# ControlPWMSin.net
KiCad netlist of a schematic drawn in Altium Designer
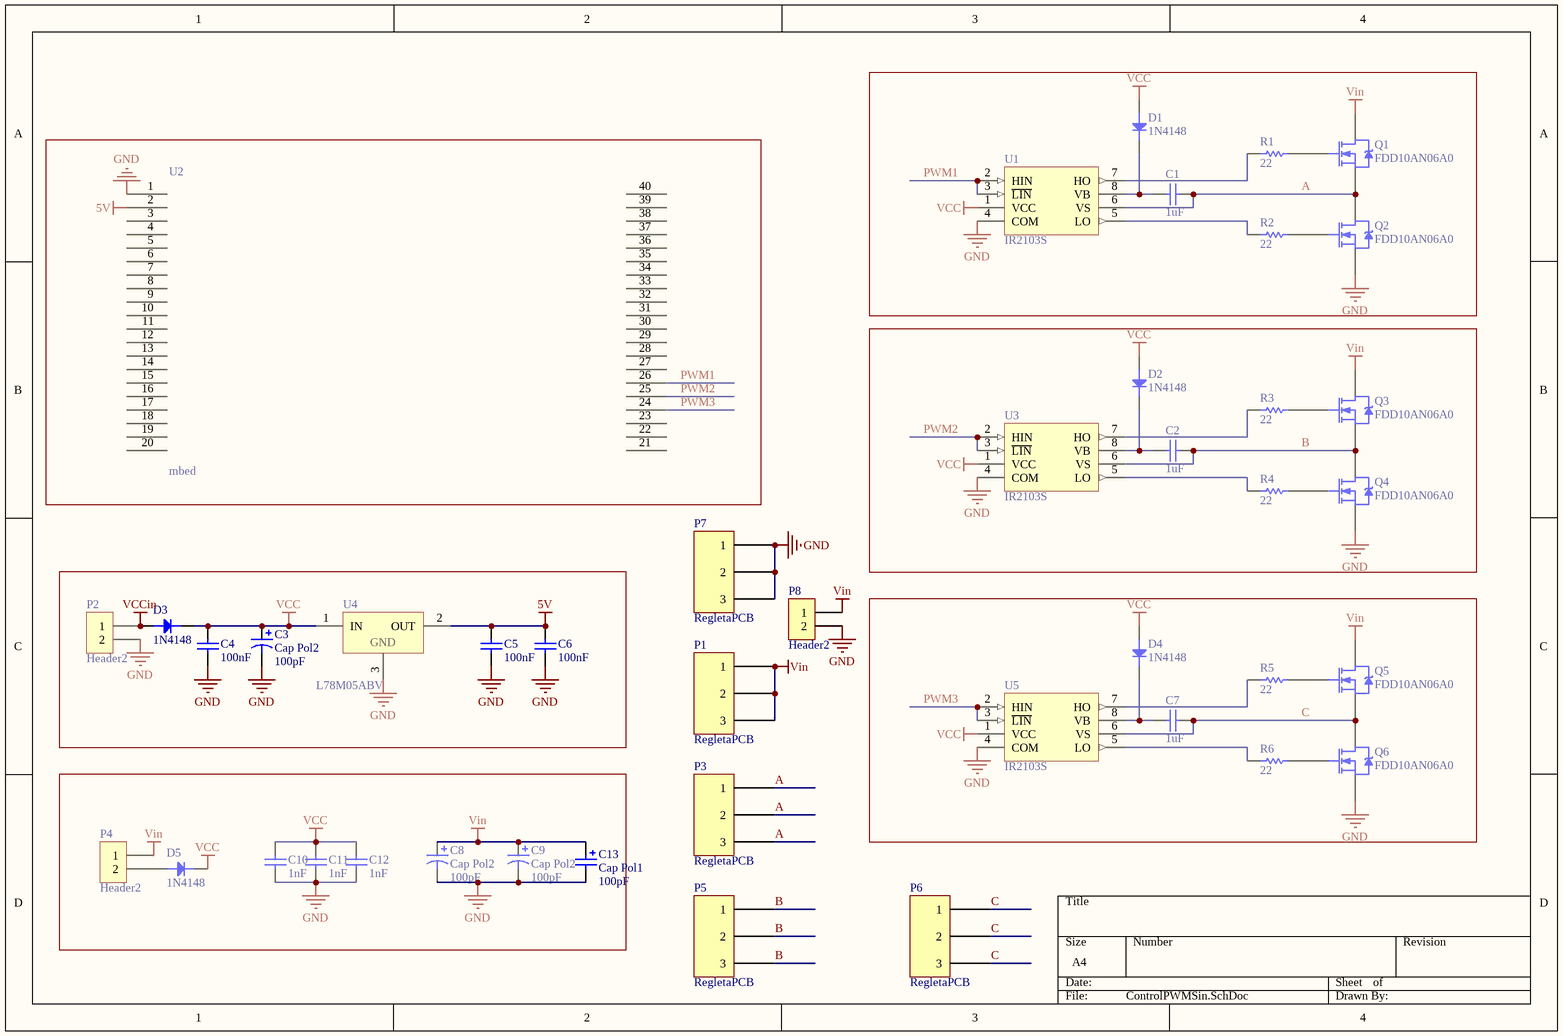
[diagram p0: ControlPWMSin.SchDoc]

(export (version "E")
  (design (tool "Eeschema 10.0.6"))
  (components
    (comp (ref "C1")
      (value "1uF")
      (footprint "0805_CAP")
      (fields (field (name "Comment") "Capacitor"))
      (libsource (lib "epf") (part "Cap"))
    )
    (comp (ref "C2")
      (value "1uF")
      (footprint "0805_CAP")
      (fields (field (name "Comment") "Capacitor"))
      (libsource (lib "epf") (part "Cap"))
    )
    (comp (ref "C3")
      (value "Cap Pol2")
      (footprint "TC7360-2924")
      (description "Polarized Capacitor (Axial)")
      (fields (field (name "ALTIUM_VALUE") "100pF") (field (name "PUBLISHER") "Altium Limited"))
      (libsource (lib "epf") (part "Cap Pol2"))
    )
    (comp (ref "C4")
      (value "100nF")
      (footprint "0805_CAP")
      (fields (field (name "Comment") "Capacitor"))
      (libsource (lib "epf") (part "Cap"))
    )
    (comp (ref "C5")
      (value "100nF")
      (footprint "0805_CAP")
      (fields (field (name "Comment") "Capacitor"))
      (libsource (lib "epf") (part "Cap"))
    )
    (comp (ref "C6")
      (value "100nF")
      (footprint "0805_CAP")
      (fields (field (name "Comment") "Capacitor"))
      (libsource (lib "epf") (part "Cap"))
    )
    (comp (ref "C7")
      (value "1uF")
      (footprint "0805_CAP")
      (fields (field (name "Comment") "Capacitor"))
      (libsource (lib "epf") (part "Cap"))
    )
    (comp (ref "C8")
      (value "Cap Pol2")
      (footprint "TC7360-2924")
      (description "Polarized Capacitor (Axial)")
      (fields (field (name "ALTIUM_VALUE") "100pF") (field (name "PUBLISHER") "Altium Limited"))
      (libsource (lib "epf") (part "Cap Pol2"))
    )
    (comp (ref "C9")
      (value "Cap Pol2")
      (footprint "TC7360-2924")
      (description "Polarized Capacitor (Axial)")
      (fields (field (name "ALTIUM_VALUE") "100pF") (field (name "PUBLISHER") "Altium Limited"))
      (libsource (lib "epf") (part "Cap Pol2"))
    )
    (comp (ref "C10")
      (value "1nF")
      (footprint "0805_CAP")
      (fields (field (name "Comment") "Capacitor"))
      (libsource (lib "epf") (part "Cap"))
    )
    (comp (ref "C11")
      (value "1nF")
      (footprint "0805_CAP")
      (fields (field (name "Comment") "Capacitor"))
      (libsource (lib "epf") (part "Cap"))
    )
    (comp (ref "C12")
      (value "1nF")
      (footprint "0805_CAP")
      (fields (field (name "Comment") "Capacitor"))
      (libsource (lib "epf") (part "Cap"))
    )
    (comp (ref "C13")
      (value "Cap Pol1")
      (footprint "RB7.6-15")
      (description "Polarized Capacitor (Radial)")
      (fields (field (name "ALTIUM_VALUE") "100pF") (field (name "PUBLISHER") "Altium Limited"))
      (libsource (lib "epf") (part "Cap Pol1"))
    )
    (comp (ref "D1") (value "1N4148") (footprint "1N4148SMD") (libsource (lib "epf") (part "1N4148")))
    (comp (ref "D2") (value "1N4148") (footprint "1N4148SMD") (libsource (lib "epf") (part "1N4148")))
    (comp (ref "D3") (value "1N4148") (footprint "1N4148SMD") (libsource (lib "epf") (part "1N4148")))
    (comp (ref "D4") (value "1N4148") (footprint "1N4148SMD") (libsource (lib "epf") (part "1N4148")))
    (comp (ref "D5") (value "1N4148") (footprint "1N4148SMD") (libsource (lib "epf") (part "1N4148")))
    (comp (ref "P1")
      (value "RegletaPCB")
      (footprint "RegletaPCBx3")
      (libsource (lib "epf") (part "RegletaPCBx3"))
    )
    (comp (ref "P2") (value "Header2") (footprint "Header2Macho") (libsource (lib "epf") (part "Header2")))
    (comp (ref "P3")
      (value "RegletaPCB")
      (footprint "RegletaPCBx3")
      (libsource (lib "epf") (part "RegletaPCBx3"))
    )
    (comp (ref "P4") (value "Header2") (footprint "Header2Macho") (libsource (lib "epf") (part "Header2")))
    (comp (ref "P5")
      (value "RegletaPCB")
      (footprint "RegletaPCBx3")
      (libsource (lib "epf") (part "RegletaPCBx3"))
    )
    (comp (ref "P6")
      (value "RegletaPCB")
      (footprint "RegletaPCBx3")
      (libsource (lib "epf") (part "RegletaPCBx3"))
    )
    (comp (ref "P7")
      (value "RegletaPCB")
      (footprint "RegletaPCBx3")
      (libsource (lib "epf") (part "RegletaPCBx3"))
    )
    (comp (ref "P8") (value "Header2") (footprint "Header2Macho") (libsource (lib "epf") (part "Header2")))
    (comp (ref "Q1")
      (value "FDD10AN06A0")
      (footprint "TO252-3N")
      (description "N-Channel Power MOSFET")
      (fields (field (name "PUBLISHER") "Altium Limited"))
      (libsource (lib "epf") (part "FDD10AN06A0"))
    )
    (comp (ref "Q2")
      (value "FDD10AN06A0")
      (footprint "TO252-3N")
      (description "N-Channel Power MOSFET")
      (fields (field (name "PUBLISHER") "Altium Limited"))
      (libsource (lib "epf") (part "FDD10AN06A0"))
    )
    (comp (ref "Q3")
      (value "FDD10AN06A0")
      (footprint "TO252-3N")
      (description "N-Channel Power MOSFET")
      (fields (field (name "PUBLISHER") "Altium Limited"))
      (libsource (lib "epf") (part "FDD10AN06A0"))
    )
    (comp (ref "Q4")
      (value "FDD10AN06A0")
      (footprint "TO252-3N")
      (description "N-Channel Power MOSFET")
      (fields (field (name "PUBLISHER") "Altium Limited"))
      (libsource (lib "epf") (part "FDD10AN06A0"))
    )
    (comp (ref "Q5")
      (value "FDD10AN06A0")
      (footprint "TO252-3N")
      (description "N-Channel Power MOSFET")
      (fields (field (name "PUBLISHER") "Altium Limited"))
      (libsource (lib "epf") (part "FDD10AN06A0"))
    )
    (comp (ref "Q6")
      (value "FDD10AN06A0")
      (footprint "TO252-3N")
      (description "N-Channel Power MOSFET")
      (fields (field (name "PUBLISHER") "Altium Limited"))
      (libsource (lib "epf") (part "FDD10AN06A0"))
    )
    (comp (ref "R1")
      (value "22")
      (footprint "0805_RES")
      (fields (field (name "Comment") "Resistor"))
      (libsource (lib "epf") (part "Res"))
    )
    (comp (ref "R2")
      (value "22")
      (footprint "0805_RES")
      (fields (field (name "Comment") "Resistor"))
      (libsource (lib "epf") (part "Res"))
    )
    (comp (ref "R3")
      (value "22")
      (footprint "0805_RES")
      (fields (field (name "Comment") "Resistor"))
      (libsource (lib "epf") (part "Res"))
    )
    (comp (ref "R4")
      (value "22")
      (footprint "0805_RES")
      (fields (field (name "Comment") "Resistor"))
      (libsource (lib "epf") (part "Res"))
    )
    (comp (ref "R5")
      (value "22")
      (footprint "0805_RES")
      (fields (field (name "Comment") "Resistor"))
      (libsource (lib "epf") (part "Res"))
    )
    (comp (ref "R6")
      (value "22")
      (footprint "0805_RES")
      (fields (field (name "Comment") "Resistor"))
      (libsource (lib "epf") (part "Res"))
    )
    (comp (ref "U1")
      (value "IR2103S")
      (footprint "SOIC127P600-8BN")
      (description "High and Low Side Driver")
      (fields (field (name "PUBLISHER") "Altium Limited"))
      (libsource (lib "epf") (part "IR2103S"))
    )
    (comp (ref "U2") (value "mbed") (footprint "mbed") (libsource (lib "epf") (part "mbed")))
    (comp (ref "U3")
      (value "IR2103S")
      (footprint "SOIC127P600-8BN")
      (description "High and Low Side Driver")
      (fields (field (name "PUBLISHER") "Altium Limited"))
      (libsource (lib "epf") (part "IR2103S"))
    )
    (comp (ref "U4")
      (value "L78M05ABV")
      (footprint "TO220V")
      (description "Precision 500mA Regulator")
      (fields (field (name "PUBLISHER") "Altium Limited"))
      (libsource (lib "epf") (part "L78M05ABV"))
    )
    (comp (ref "U5")
      (value "IR2103S")
      (footprint "SOIC127P600-8BN")
      (description "High and Low Side Driver")
      (fields (field (name "PUBLISHER") "Altium Limited"))
      (libsource (lib "epf") (part "IR2103S"))
    )
  )
  (nets
    (net (code "1") (name "/A") (class "Default")
      (node (ref "C1") (pin "1") (pinfunction "1_1") (pintype "passive"))
      (node (ref "P3") (pin "1") (pinfunction "1_1") (pintype "passive"))
      (node (ref "P3") (pin "2") (pinfunction "2_2") (pintype "passive"))
      (node (ref "P3") (pin "3") (pinfunction "3_3") (pintype "passive"))
      (node (ref "Q1") (pin "3") (pinfunction "S_3") (pintype "passive"))
      (node (ref "Q2") (pin "4") (pinfunction "D_4") (pintype "passive"))
      (node (ref "U1") (pin "6") (pinfunction "VS_6") (pintype "power_in"))
    )
    (net (code "2") (name "/B") (class "Default")
      (node (ref "C2") (pin "1") (pinfunction "1_1") (pintype "passive"))
      (node (ref "P5") (pin "1") (pinfunction "1_1") (pintype "passive"))
      (node (ref "P5") (pin "2") (pinfunction "2_2") (pintype "passive"))
      (node (ref "P5") (pin "3") (pinfunction "3_3") (pintype "passive"))
      (node (ref "Q3") (pin "3") (pinfunction "S_3") (pintype "passive"))
      (node (ref "Q4") (pin "4") (pinfunction "D_4") (pintype "passive"))
      (node (ref "U3") (pin "6") (pinfunction "VS_6") (pintype "power_in"))
    )
    (net (code "3") (name "/C") (class "Default")
      (node (ref "C7") (pin "1") (pinfunction "1_1") (pintype "passive"))
      (node (ref "P6") (pin "1") (pinfunction "1_1") (pintype "passive"))
      (node (ref "P6") (pin "2") (pinfunction "2_2") (pintype "passive"))
      (node (ref "P6") (pin "3") (pinfunction "3_3") (pintype "passive"))
      (node (ref "Q5") (pin "3") (pinfunction "S_3") (pintype "passive"))
      (node (ref "Q6") (pin "4") (pinfunction "D_4") (pintype "passive"))
      (node (ref "U5") (pin "6") (pinfunction "VS_6") (pintype "power_in"))
    )
    (net (code "4") (name "/PWM1") (class "Default")
      (node (ref "U1") (pin "2") (pinfunction "HIN_2") (pintype "input"))
      (node (ref "U1") (pin "3") (pinfunction "~{LIN}_3") (pintype "input"))
      (node (ref "U2") (pin "26") (pinfunction "26_26") (pintype "passive"))
    )
    (net (code "5") (name "/PWM2") (class "Default")
      (node (ref "U2") (pin "25") (pinfunction "25_25") (pintype "passive"))
      (node (ref "U3") (pin "2") (pinfunction "HIN_2") (pintype "input"))
      (node (ref "U3") (pin "3") (pinfunction "~{LIN}_3") (pintype "input"))
    )
    (net (code "6") (name "/PWM3") (class "Default")
      (node (ref "U2") (pin "24") (pinfunction "24_24") (pintype "passive"))
      (node (ref "U5") (pin "2") (pinfunction "HIN_2") (pintype "input"))
      (node (ref "U5") (pin "3") (pinfunction "~{LIN}_3") (pintype "input"))
    )
    (net (code "7") (name "5V") (class "Default")
      (node (ref "C5") (pin "1") (pinfunction "1_1") (pintype "passive"))
      (node (ref "C6") (pin "1") (pinfunction "1_1") (pintype "passive"))
      (node (ref "U2") (pin "2") (pinfunction "2_2") (pintype "passive"))
      (node (ref "U4") (pin "2") (pinfunction "OUT_2") (pintype "power_in"))
    )
    (net (code "8") (name "GND") (class "Default")
      (node (ref "C10") (pin "1") (pinfunction "1_1") (pintype "passive"))
      (node (ref "C11") (pin "1") (pinfunction "1_1") (pintype "passive"))
      (node (ref "C12") (pin "1") (pinfunction "1_1") (pintype "passive"))
      (node (ref "C13") (pin "2") (pinfunction "2_2") (pintype "passive"))
      (node (ref "C3") (pin "2") (pinfunction "2_2") (pintype "passive"))
      (node (ref "C4") (pin "2") (pinfunction "2_2") (pintype "passive"))
      (node (ref "C5") (pin "2") (pinfunction "2_2") (pintype "passive"))
      (node (ref "C6") (pin "2") (pinfunction "2_2") (pintype "passive"))
      (node (ref "C8") (pin "2") (pinfunction "2_2") (pintype "passive"))
      (node (ref "C9") (pin "2") (pinfunction "2_2") (pintype "passive"))
      (node (ref "P2") (pin "2") (pinfunction "2_2") (pintype "passive"))
      (node (ref "P7") (pin "1") (pinfunction "1_1") (pintype "passive"))
      (node (ref "P7") (pin "2") (pinfunction "2_2") (pintype "passive"))
      (node (ref "P7") (pin "3") (pinfunction "3_3") (pintype "passive"))
      (node (ref "P8") (pin "2") (pinfunction "2_2") (pintype "passive"))
      (node (ref "Q2") (pin "3") (pinfunction "S_3") (pintype "passive"))
      (node (ref "Q4") (pin "3") (pinfunction "S_3") (pintype "passive"))
      (node (ref "Q6") (pin "3") (pinfunction "S_3") (pintype "passive"))
      (node (ref "U1") (pin "4") (pinfunction "COM_4") (pintype "power_in"))
      (node (ref "U2") (pin "1") (pinfunction "1_1") (pintype "passive"))
      (node (ref "U3") (pin "4") (pinfunction "COM_4") (pintype "power_in"))
      (node (ref "U4") (pin "3") (pinfunction "GND_3") (pintype "power_in"))
      (node (ref "U5") (pin "4") (pinfunction "COM_4") (pintype "power_in"))
    )
    (net (code "9") (name "Net-(D1-K)") (class "Default")
      (node (ref "C1") (pin "2") (pinfunction "2_2") (pintype "passive"))
      (node (ref "D1") (pin "2") (pinfunction "K_2") (pintype "passive"))
      (node (ref "U1") (pin "8") (pinfunction "VB_8") (pintype "power_in"))
    )
    (net (code "10") (name "Net-(D2-K)") (class "Default")
      (node (ref "C2") (pin "2") (pinfunction "2_2") (pintype "passive"))
      (node (ref "D2") (pin "2") (pinfunction "K_2") (pintype "passive"))
      (node (ref "U3") (pin "8") (pinfunction "VB_8") (pintype "power_in"))
    )
    (net (code "11") (name "Net-(D4-K)") (class "Default")
      (node (ref "C7") (pin "2") (pinfunction "2_2") (pintype "passive"))
      (node (ref "D4") (pin "2") (pinfunction "K_2") (pintype "passive"))
      (node (ref "U5") (pin "8") (pinfunction "VB_8") (pintype "power_in"))
    )
    (net (code "12") (name "Net-(D5-A)") (class "Default")
      (node (ref "D5") (pin "1") (pinfunction "A_1") (pintype "passive"))
      (node (ref "P4") (pin "2") (pinfunction "2_2") (pintype "passive"))
    )
    (net (code "13") (name "Net-(Q1-G)") (class "Default")
      (node (ref "Q1") (pin "1") (pinfunction "G_1") (pintype "passive"))
      (node (ref "R1") (pin "2") (pinfunction "2_2") (pintype "passive"))
    )
    (net (code "14") (name "Net-(Q2-G)") (class "Default")
      (node (ref "Q2") (pin "1") (pinfunction "G_1") (pintype "passive"))
      (node (ref "R2") (pin "2") (pinfunction "2_2") (pintype "passive"))
    )
    (net (code "15") (name "Net-(Q3-G)") (class "Default")
      (node (ref "Q3") (pin "1") (pinfunction "G_1") (pintype "passive"))
      (node (ref "R3") (pin "2") (pinfunction "2_2") (pintype "passive"))
    )
    (net (code "16") (name "Net-(Q4-G)") (class "Default")
      (node (ref "Q4") (pin "1") (pinfunction "G_1") (pintype "passive"))
      (node (ref "R4") (pin "2") (pinfunction "2_2") (pintype "passive"))
    )
    (net (code "17") (name "Net-(Q5-G)") (class "Default")
      (node (ref "Q5") (pin "1") (pinfunction "G_1") (pintype "passive"))
      (node (ref "R5") (pin "2") (pinfunction "2_2") (pintype "passive"))
    )
    (net (code "18") (name "Net-(Q6-G)") (class "Default")
      (node (ref "Q6") (pin "1") (pinfunction "G_1") (pintype "passive"))
      (node (ref "R6") (pin "2") (pinfunction "2_2") (pintype "passive"))
    )
    (net (code "19") (name "Net-(U1-HO)") (class "Default")
      (node (ref "R1") (pin "1") (pinfunction "1_1") (pintype "passive"))
      (node (ref "U1") (pin "7") (pinfunction "HO_7") (pintype "output"))
    )
    (net (code "20") (name "Net-(U1-LO)") (class "Default")
      (node (ref "R2") (pin "1") (pinfunction "1_1") (pintype "passive"))
      (node (ref "U1") (pin "5") (pinfunction "LO_5") (pintype "output"))
    )
    (net (code "21") (name "Net-(U3-HO)") (class "Default")
      (node (ref "R3") (pin "1") (pinfunction "1_1") (pintype "passive"))
      (node (ref "U3") (pin "7") (pinfunction "HO_7") (pintype "output"))
    )
    (net (code "22") (name "Net-(U3-LO)") (class "Default")
      (node (ref "R4") (pin "1") (pinfunction "1_1") (pintype "passive"))
      (node (ref "U3") (pin "5") (pinfunction "LO_5") (pintype "output"))
    )
    (net (code "23") (name "Net-(U5-HO)") (class "Default")
      (node (ref "R5") (pin "1") (pinfunction "1_1") (pintype "passive"))
      (node (ref "U5") (pin "7") (pinfunction "HO_7") (pintype "output"))
    )
    (net (code "24") (name "Net-(U5-LO)") (class "Default")
      (node (ref "R6") (pin "1") (pinfunction "1_1") (pintype "passive"))
      (node (ref "U5") (pin "5") (pinfunction "LO_5") (pintype "output"))
    )
    (net (code "25") (name "VCC") (class "Default")
      (node (ref "C10") (pin "2") (pinfunction "2_2") (pintype "passive"))
      (node (ref "C11") (pin "2") (pinfunction "2_2") (pintype "passive"))
      (node (ref "C12") (pin "2") (pinfunction "2_2") (pintype "passive"))
      (node (ref "C3") (pin "1") (pinfunction "1_1") (pintype "passive"))
      (node (ref "C4") (pin "1") (pinfunction "1_1") (pintype "passive"))
      (node (ref "D1") (pin "1") (pinfunction "A_1") (pintype "passive"))
      (node (ref "D2") (pin "1") (pinfunction "A_1") (pintype "passive"))
      (node (ref "D3") (pin "2") (pinfunction "K_2") (pintype "passive"))
      (node (ref "D4") (pin "1") (pinfunction "A_1") (pintype "passive"))
      (node (ref "D5") (pin "2") (pinfunction "K_2") (pintype "passive"))
      (node (ref "U1") (pin "1") (pinfunction "VCC_1") (pintype "power_in"))
      (node (ref "U3") (pin "1") (pinfunction "VCC_1") (pintype "power_in"))
      (node (ref "U4") (pin "1") (pinfunction "IN_1") (pintype "power_in"))
      (node (ref "U5") (pin "1") (pinfunction "VCC_1") (pintype "power_in"))
    )
    (net (code "26") (name "VCCin") (class "Default")
      (node (ref "D3") (pin "1") (pinfunction "A_1") (pintype "passive"))
      (node (ref "P2") (pin "1") (pinfunction "1_1") (pintype "passive"))
    )
    (net (code "27") (name "Vin") (class "Default")
      (node (ref "C13") (pin "1") (pinfunction "1_1") (pintype "passive"))
      (node (ref "C8") (pin "1") (pinfunction "1_1") (pintype "passive"))
      (node (ref "C9") (pin "1") (pinfunction "1_1") (pintype "passive"))
      (node (ref "P1") (pin "1") (pinfunction "1_1") (pintype "passive"))
      (node (ref "P1") (pin "2") (pinfunction "2_2") (pintype "passive"))
      (node (ref "P1") (pin "3") (pinfunction "3_3") (pintype "passive"))
      (node (ref "P4") (pin "1") (pinfunction "1_1") (pintype "passive"))
      (node (ref "P8") (pin "1") (pinfunction "1_1") (pintype "passive"))
      (node (ref "Q1") (pin "4") (pinfunction "D_4") (pintype "passive"))
      (node (ref "Q3") (pin "4") (pinfunction "D_4") (pintype "passive"))
      (node (ref "Q5") (pin "4") (pinfunction "D_4") (pintype "passive"))
    )
    (net (code "28") (name "unconnected-(U2-Pad3)") (class "Default")
      (node (ref "U2") (pin "3") (pinfunction "3_3") (pintype "passive"))
    )
    (net (code "29") (name "unconnected-(U2-Pad4)") (class "Default")
      (node (ref "U2") (pin "4") (pinfunction "4_4") (pintype "passive"))
    )
    (net (code "30") (name "unconnected-(U2-Pad5)") (class "Default")
      (node (ref "U2") (pin "5") (pinfunction "5_5") (pintype "passive"))
    )
    (net (code "31") (name "unconnected-(U2-Pad6)") (class "Default")
      (node (ref "U2") (pin "6") (pinfunction "6_6") (pintype "passive"))
    )
    (net (code "32") (name "unconnected-(U2-Pad7)") (class "Default")
      (node (ref "U2") (pin "7") (pinfunction "7_7") (pintype "passive"))
    )
    (net (code "33") (name "unconnected-(U2-Pad8)") (class "Default")
      (node (ref "U2") (pin "8") (pinfunction "8_8") (pintype "passive"))
    )
    (net (code "34") (name "unconnected-(U2-Pad9)") (class "Default")
      (node (ref "U2") (pin "9") (pinfunction "9_9") (pintype "passive"))
    )
    (net (code "35") (name "unconnected-(U2-Pad10)") (class "Default")
      (node (ref "U2") (pin "10") (pinfunction "10_10") (pintype "passive"))
    )
    (net (code "36") (name "unconnected-(U2-Pad11)") (class "Default")
      (node (ref "U2") (pin "11") (pinfunction "11_11") (pintype "passive"))
    )
    (net (code "37") (name "unconnected-(U2-Pad12)") (class "Default")
      (node (ref "U2") (pin "12") (pinfunction "12_12") (pintype "passive"))
    )
    (net (code "38") (name "unconnected-(U2-Pad13)") (class "Default")
      (node (ref "U2") (pin "13") (pinfunction "13_13") (pintype "passive"))
    )
    (net (code "39") (name "unconnected-(U2-Pad14)") (class "Default")
      (node (ref "U2") (pin "14") (pinfunction "14_14") (pintype "passive"))
    )
    (net (code "40") (name "unconnected-(U2-Pad15)") (class "Default")
      (node (ref "U2") (pin "15") (pinfunction "15_15") (pintype "passive"))
    )
    (net (code "41") (name "unconnected-(U2-Pad16)") (class "Default")
      (node (ref "U2") (pin "16") (pinfunction "16_16") (pintype "passive"))
    )
    (net (code "42") (name "unconnected-(U2-Pad17)") (class "Default")
      (node (ref "U2") (pin "17") (pinfunction "17_17") (pintype "passive"))
    )
    (net (code "43") (name "unconnected-(U2-Pad18)") (class "Default")
      (node (ref "U2") (pin "18") (pinfunction "18_18") (pintype "passive"))
    )
    (net (code "44") (name "unconnected-(U2-Pad19)") (class "Default")
      (node (ref "U2") (pin "19") (pinfunction "19_19") (pintype "passive"))
    )
    (net (code "45") (name "unconnected-(U2-Pad20)") (class "Default")
      (node (ref "U2") (pin "20") (pinfunction "20_20") (pintype "passive"))
    )
    (net (code "46") (name "unconnected-(U2-Pad21)") (class "Default")
      (node (ref "U2") (pin "21") (pinfunction "21_21") (pintype "passive"))
    )
    (net (code "47") (name "unconnected-(U2-Pad22)") (class "Default")
      (node (ref "U2") (pin "22") (pinfunction "22_22") (pintype "passive"))
    )
    (net (code "48") (name "unconnected-(U2-Pad23)") (class "Default")
      (node (ref "U2") (pin "23") (pinfunction "23_23") (pintype "passive"))
    )
    (net (code "49") (name "unconnected-(U2-Pad27)") (class "Default")
      (node (ref "U2") (pin "27") (pinfunction "27_27") (pintype "passive"))
    )
    (net (code "50") (name "unconnected-(U2-Pad28)") (class "Default")
      (node (ref "U2") (pin "28") (pinfunction "28_28") (pintype "passive"))
    )
    (net (code "51") (name "unconnected-(U2-Pad29)") (class "Default")
      (node (ref "U2") (pin "29") (pinfunction "29_29") (pintype "passive"))
    )
    (net (code "52") (name "unconnected-(U2-Pad30)") (class "Default")
      (node (ref "U2") (pin "30") (pinfunction "30_30") (pintype "passive"))
    )
    (net (code "53") (name "unconnected-(U2-Pad31)") (class "Default")
      (node (ref "U2") (pin "31") (pinfunction "31_31") (pintype "passive"))
    )
    (net (code "54") (name "unconnected-(U2-Pad32)") (class "Default")
      (node (ref "U2") (pin "32") (pinfunction "32_32") (pintype "passive"))
    )
    (net (code "55") (name "unconnected-(U2-Pad33)") (class "Default")
      (node (ref "U2") (pin "33") (pinfunction "33_33") (pintype "passive"))
    )
    (net (code "56") (name "unconnected-(U2-Pad34)") (class "Default")
      (node (ref "U2") (pin "34") (pinfunction "34_34") (pintype "passive"))
    )
    (net (code "57") (name "unconnected-(U2-Pad35)") (class "Default")
      (node (ref "U2") (pin "35") (pinfunction "35_35") (pintype "passive"))
    )
    (net (code "58") (name "unconnected-(U2-Pad36)") (class "Default")
      (node (ref "U2") (pin "36") (pinfunction "36_36") (pintype "passive"))
    )
    (net (code "59") (name "unconnected-(U2-Pad37)") (class "Default")
      (node (ref "U2") (pin "37") (pinfunction "37_37") (pintype "passive"))
    )
    (net (code "60") (name "unconnected-(U2-Pad38)") (class "Default")
      (node (ref "U2") (pin "38") (pinfunction "38_38") (pintype "passive"))
    )
    (net (code "61") (name "unconnected-(U2-Pad39)") (class "Default")
      (node (ref "U2") (pin "39") (pinfunction "39_39") (pintype "passive"))
    )
    (net (code "62") (name "unconnected-(U2-Pad40)") (class "Default")
      (node (ref "U2") (pin "40") (pinfunction "40_40") (pintype "passive"))
    )
  )
)
